# SCH_NFC-Card-Nilaan_2024-10-09.net
KiCad netlist of a schematic drawn in EasyEDA
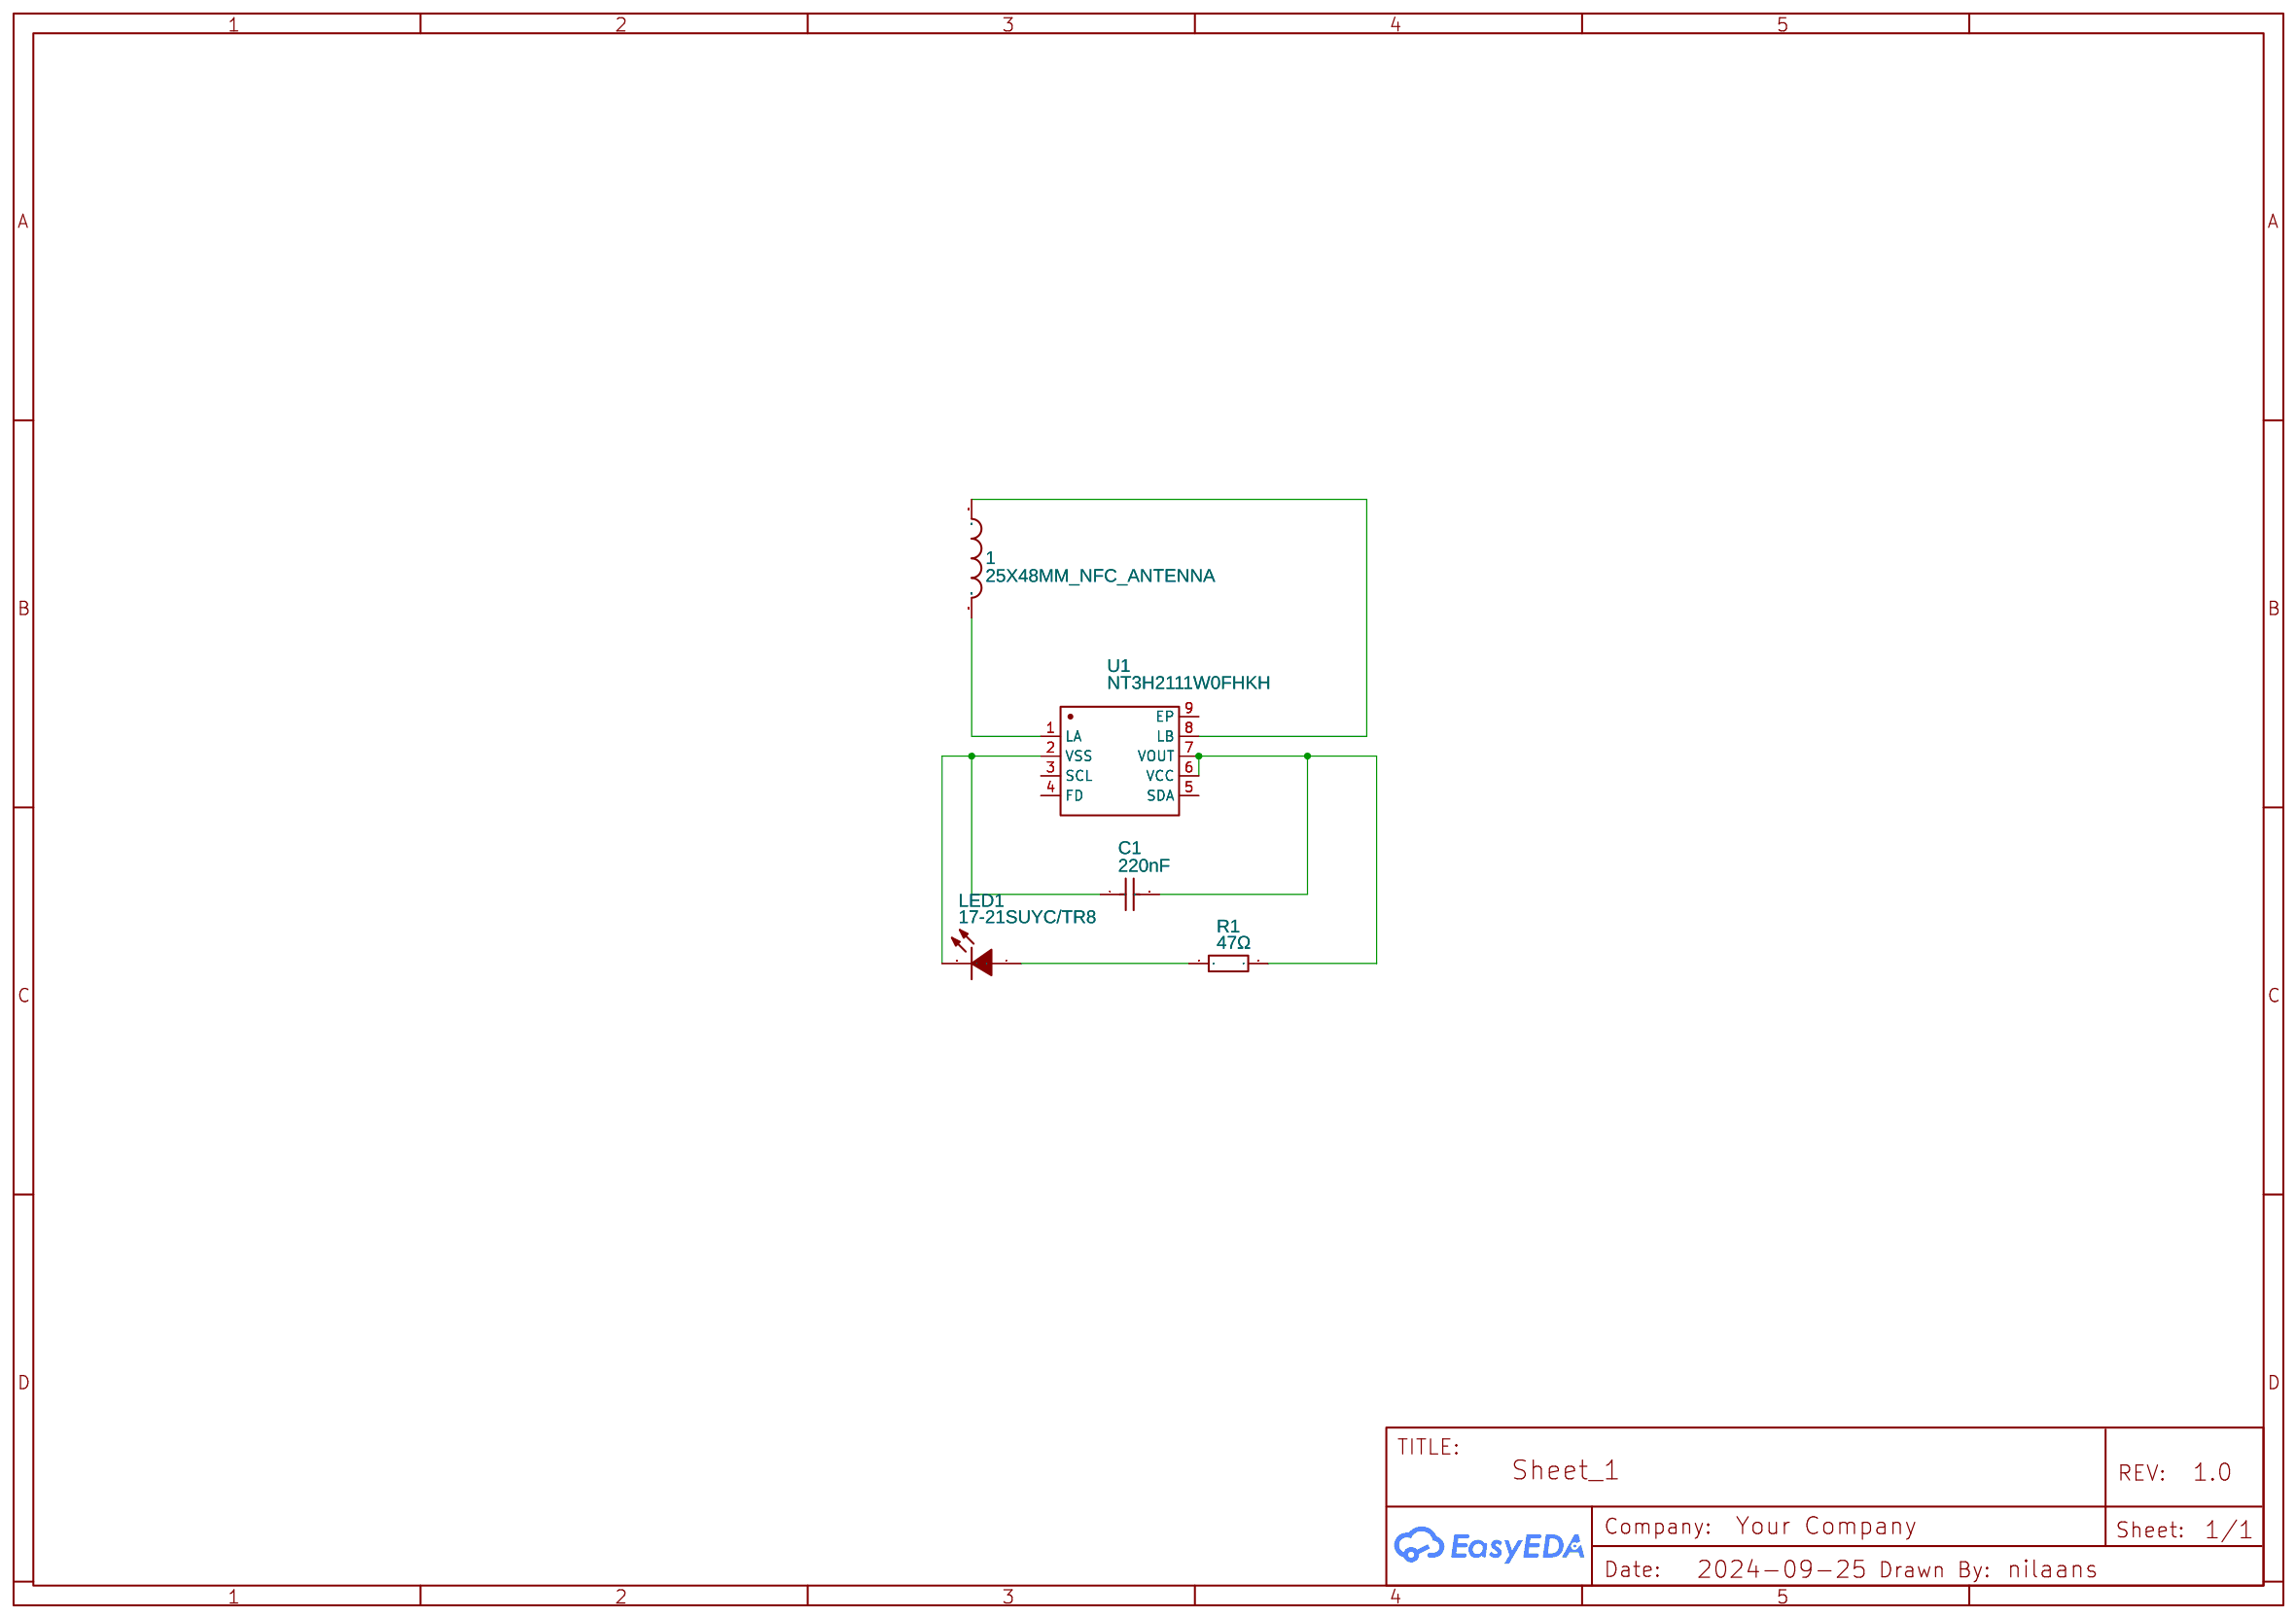
[diagram p0: schematic sheet]

(export (version "E")
  (design (tool "Eeschema 10.0.6"))
  (components
    (comp (ref "1") (value "25X48MM_NFC_ANTENNA") (libsource (lib "") (part "25X48MM_NFC_ANTENNA")))
    (comp (ref "C1")
      (value "220nF")
      (fields
        (field (name "Manufacturer Part") "CL10B224KA8NNNC")
        (field (name "Manufacturer") "SAMSUNG(三星)")
      )
      (libsource (lib "") (part "CL10B224KA8NNNC"))
    )
    (comp (ref "LED1")
      (value "17-21SUYC/TR8")
      (fields (field (name "Manufacturer Part") "KT-0805黄灯") (field (name "Manufacturer") "KENTO"))
      (libsource (lib "") (part "17-21SUYC/TR8"))
    )
    (comp (ref "R1")
      (value "47Ω")
      (fields
        (field (name "Manufacturer Part") "0603WAF470JT5E")
        (field (name "Manufacturer") "UNI-ROYAL(厚声)")
      )
      (libsource (lib "") (part "0603WAF470JT5E"))
    )
    (comp (ref "U1")
      (value "NT3H2111W0FHKH")
      (fields (field (name "Manufacturer") "NXP(恩智浦)"))
      (libsource (lib "") (part "NT3H2111W0FHKH"))
    )
  )
  (nets
    (net (code "1") (name "Net-(LED1-+)") (class "Default")
      (node (ref "LED1") (pin "1") (pinfunction "+_1") (pintype "unspecified"))
      (node (ref "R1") (pin "1") (pinfunction "1_1") (pintype "input"))
    )
    (net (code "2") (name "Net-(LED1--)") (class "Default")
      (node (ref "C1") (pin "1") (pinfunction "1_1") (pintype "input"))
      (node (ref "LED1") (pin "2") (pinfunction "-_2") (pintype "unspecified"))
      (node (ref "U1") (pin "2") (pinfunction "VSS_2") (pintype "unspecified"))
    )
    (net (code "3") (name "Net-(U1-LA)") (class "Default")
      (node (ref "1") (pin "P$2") (pinfunction "P$2_P$2") (pintype "bidirectional"))
      (node (ref "U1") (pin "1") (pinfunction "LA_1") (pintype "unspecified"))
    )
    (net (code "4") (name "Net-(U1-LB)") (class "Default")
      (node (ref "1") (pin "P$1") (pinfunction "P$1_P$1") (pintype "bidirectional"))
      (node (ref "U1") (pin "8") (pinfunction "LB_8") (pintype "unspecified"))
    )
    (net (code "5") (name "Net-(U1-VCC)") (class "Default")
      (node (ref "C1") (pin "2") (pinfunction "2_2") (pintype "input"))
      (node (ref "R1") (pin "2") (pinfunction "2_2") (pintype "input"))
      (node (ref "U1") (pin "6") (pinfunction "VCC_6") (pintype "unspecified"))
      (node (ref "U1") (pin "7") (pinfunction "VOUT_7") (pintype "unspecified"))
    )
    (net (code "6") (name "unconnected-(U1-EP-Pad9)") (class "Default")
      (node (ref "U1") (pin "9") (pinfunction "EP_9") (pintype "unspecified"))
    )
    (net (code "7") (name "unconnected-(U1-FD-Pad4)") (class "Default")
      (node (ref "U1") (pin "4") (pinfunction "FD_4") (pintype "unspecified"))
    )
    (net (code "8") (name "unconnected-(U1-SCL-Pad3)") (class "Default")
      (node (ref "U1") (pin "3") (pinfunction "SCL_3") (pintype "unspecified"))
    )
    (net (code "9") (name "unconnected-(U1-SDA-Pad5)") (class "Default")
      (node (ref "U1") (pin "5") (pinfunction "SDA_5") (pintype "unspecified"))
    )
  )
)
